# drv.net
KiCad netlist of a schematic drawn in Altium Designer
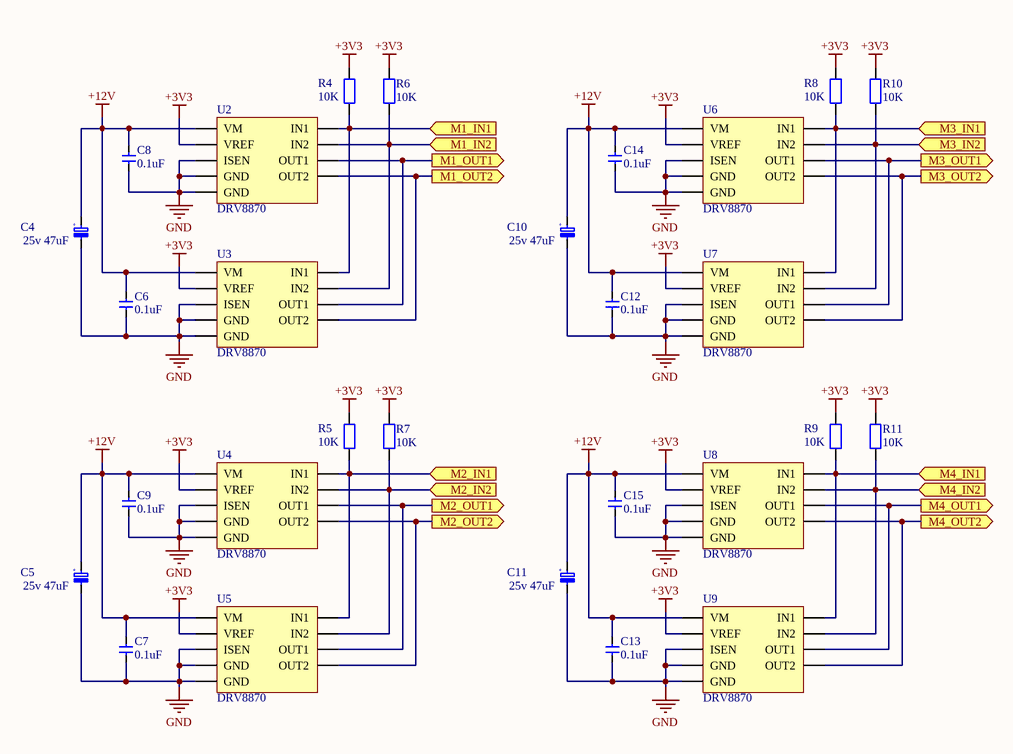
[diagram p0: drv.SchDoc]

(export (version "E")
  (design (tool "Eeschema 10.0.6"))
  (components
    (comp (ref "C4")
      (value "25v 47uF")
      (footprint "CAP_TANT_D")
      (description "Tantal SMD Cap")
      (libsource (lib "Asterisk") (part "CAP Tantal"))
    )
    (comp (ref "C5")
      (value "25v 47uF")
      (footprint "CAP_TANT_D")
      (description "Tantal SMD Cap")
      (libsource (lib "Asterisk") (part "CAP Tantal"))
    )
    (comp (ref "C6")
      (value "0.1uF")
      (footprint "CAP0805")
      (description "Ceramic SMD Cap")
      (libsource (lib "Asterisk") (part "CAP Ceramic"))
    )
    (comp (ref "C7")
      (value "0.1uF")
      (footprint "CAP0805")
      (description "Ceramic SMD Cap")
      (libsource (lib "Asterisk") (part "CAP Ceramic"))
    )
    (comp (ref "C8")
      (value "0.1uF")
      (footprint "CAP0805")
      (description "Ceramic SMD Cap")
      (libsource (lib "Asterisk") (part "CAP Ceramic"))
    )
    (comp (ref "C9")
      (value "0.1uF")
      (footprint "CAP0805")
      (description "Ceramic SMD Cap")
      (libsource (lib "Asterisk") (part "CAP Ceramic"))
    )
    (comp (ref "C10")
      (value "25v 47uF")
      (footprint "CAP_TANT_D")
      (description "Tantal SMD Cap")
      (libsource (lib "Asterisk") (part "CAP Tantal"))
    )
    (comp (ref "C11")
      (value "25v 47uF")
      (footprint "CAP_TANT_D")
      (description "Tantal SMD Cap")
      (libsource (lib "Asterisk") (part "CAP Tantal"))
    )
    (comp (ref "C12")
      (value "0.1uF")
      (footprint "CAP0805")
      (description "Ceramic SMD Cap")
      (libsource (lib "Asterisk") (part "CAP Ceramic"))
    )
    (comp (ref "C13")
      (value "0.1uF")
      (footprint "CAP0805")
      (description "Ceramic SMD Cap")
      (libsource (lib "Asterisk") (part "CAP Ceramic"))
    )
    (comp (ref "C14")
      (value "0.1uF")
      (footprint "CAP0805")
      (description "Ceramic SMD Cap")
      (libsource (lib "Asterisk") (part "CAP Ceramic"))
    )
    (comp (ref "C15")
      (value "0.1uF")
      (footprint "CAP0805")
      (description "Ceramic SMD Cap")
      (libsource (lib "Asterisk") (part "CAP Ceramic"))
    )
    (comp (ref "R4")
      (value "10K")
      (footprint "RES0805")
      (description "RES smd")
      (libsource (lib "Asterisk") (part "RES"))
    )
    (comp (ref "R5")
      (value "10K")
      (footprint "RES0805")
      (description "RES smd")
      (libsource (lib "Asterisk") (part "RES"))
    )
    (comp (ref "R6")
      (value "10K")
      (footprint "RES0805")
      (description "RES smd")
      (libsource (lib "Asterisk") (part "RES"))
    )
    (comp (ref "R7")
      (value "10K")
      (footprint "RES0805")
      (description "RES smd")
      (libsource (lib "Asterisk") (part "RES"))
    )
    (comp (ref "R8")
      (value "10K")
      (footprint "RES0805")
      (description "RES smd")
      (libsource (lib "Asterisk") (part "RES"))
    )
    (comp (ref "R9")
      (value "10K")
      (footprint "RES0805")
      (description "RES smd")
      (libsource (lib "Asterisk") (part "RES"))
    )
    (comp (ref "R10")
      (value "10K")
      (footprint "RES0805")
      (description "RES smd")
      (libsource (lib "Asterisk") (part "RES"))
    )
    (comp (ref "R11")
      (value "10K")
      (footprint "RES0805")
      (description "RES smd")
      (libsource (lib "Asterisk") (part "RES"))
    )
    (comp (ref "U2")
      (value "DRV8870")
      (footprint "DRV8870")
      (description "DC motor driver 3.6A")
      (libsource (lib "Asterisk") (part "DRV8870"))
    )
    (comp (ref "U3")
      (value "DRV8870")
      (footprint "DRV8870")
      (description "DC motor driver 3.6A")
      (libsource (lib "Asterisk") (part "DRV8870"))
    )
    (comp (ref "U4")
      (value "DRV8870")
      (footprint "DRV8870")
      (description "DC motor driver 3.6A")
      (libsource (lib "Asterisk") (part "DRV8870"))
    )
    (comp (ref "U5")
      (value "DRV8870")
      (footprint "DRV8870")
      (description "DC motor driver 3.6A")
      (libsource (lib "Asterisk") (part "DRV8870"))
    )
    (comp (ref "U6")
      (value "DRV8870")
      (footprint "DRV8870")
      (description "DC motor driver 3.6A")
      (libsource (lib "Asterisk") (part "DRV8870"))
    )
    (comp (ref "U7")
      (value "DRV8870")
      (footprint "DRV8870")
      (description "DC motor driver 3.6A")
      (libsource (lib "Asterisk") (part "DRV8870"))
    )
    (comp (ref "U8")
      (value "DRV8870")
      (footprint "DRV8870")
      (description "DC motor driver 3.6A")
      (libsource (lib "Asterisk") (part "DRV8870"))
    )
    (comp (ref "U9")
      (value "DRV8870")
      (footprint "DRV8870")
      (description "DC motor driver 3.6A")
      (libsource (lib "Asterisk") (part "DRV8870"))
    )
  )
  (nets
    (net (code "1") (name "+3V3") (class "Default")
      (node (ref "R10") (pin "2") (pinfunction "2_2") (pintype "passive"))
      (node (ref "R11") (pin "2") (pinfunction "2_2") (pintype "passive"))
      (node (ref "R4") (pin "2") (pinfunction "2_2") (pintype "passive"))
      (node (ref "R5") (pin "2") (pinfunction "2_2") (pintype "passive"))
      (node (ref "R6") (pin "2") (pinfunction "2_2") (pintype "passive"))
      (node (ref "R7") (pin "2") (pinfunction "2_2") (pintype "passive"))
      (node (ref "R8") (pin "2") (pinfunction "2_2") (pintype "passive"))
      (node (ref "R9") (pin "2") (pinfunction "2_2") (pintype "passive"))
      (node (ref "U2") (pin "4") (pinfunction "VREF_4") (pintype "passive"))
      (node (ref "U3") (pin "4") (pinfunction "VREF_4") (pintype "passive"))
      (node (ref "U4") (pin "4") (pinfunction "VREF_4") (pintype "passive"))
      (node (ref "U5") (pin "4") (pinfunction "VREF_4") (pintype "passive"))
      (node (ref "U6") (pin "4") (pinfunction "VREF_4") (pintype "passive"))
      (node (ref "U7") (pin "4") (pinfunction "VREF_4") (pintype "passive"))
      (node (ref "U8") (pin "4") (pinfunction "VREF_4") (pintype "passive"))
      (node (ref "U9") (pin "4") (pinfunction "VREF_4") (pintype "passive"))
    )
    (net (code "2") (name "+12V") (class "Default")
      (node (ref "C10") (pin "2") (pinfunction "PLUS_2") (pintype "passive"))
      (node (ref "C11") (pin "2") (pinfunction "PLUS_2") (pintype "passive"))
      (node (ref "C12") (pin "2") (pinfunction "2_2") (pintype "passive"))
      (node (ref "C13") (pin "2") (pinfunction "2_2") (pintype "passive"))
      (node (ref "C14") (pin "2") (pinfunction "2_2") (pintype "passive"))
      (node (ref "C15") (pin "2") (pinfunction "2_2") (pintype "passive"))
      (node (ref "C4") (pin "2") (pinfunction "PLUS_2") (pintype "passive"))
      (node (ref "C5") (pin "2") (pinfunction "PLUS_2") (pintype "passive"))
      (node (ref "C6") (pin "2") (pinfunction "2_2") (pintype "passive"))
      (node (ref "C7") (pin "2") (pinfunction "2_2") (pintype "passive"))
      (node (ref "C8") (pin "2") (pinfunction "2_2") (pintype "passive"))
      (node (ref "C9") (pin "2") (pinfunction "2_2") (pintype "passive"))
      (node (ref "U2") (pin "5") (pinfunction "VM_5") (pintype "passive"))
      (node (ref "U3") (pin "5") (pinfunction "VM_5") (pintype "passive"))
      (node (ref "U4") (pin "5") (pinfunction "VM_5") (pintype "passive"))
      (node (ref "U5") (pin "5") (pinfunction "VM_5") (pintype "passive"))
      (node (ref "U6") (pin "5") (pinfunction "VM_5") (pintype "passive"))
      (node (ref "U7") (pin "5") (pinfunction "VM_5") (pintype "passive"))
      (node (ref "U8") (pin "5") (pinfunction "VM_5") (pintype "passive"))
      (node (ref "U9") (pin "5") (pinfunction "VM_5") (pintype "passive"))
    )
    (net (code "3") (name "/M1_IN1") (class "Default")
      (node (ref "R4") (pin "1") (pinfunction "1_1") (pintype "passive"))
      (node (ref "U2") (pin "2") (pinfunction "IN1_2") (pintype "passive"))
      (node (ref "U3") (pin "2") (pinfunction "IN1_2") (pintype "passive"))
    )
    (net (code "4") (name "/M1_IN2") (class "Default")
      (node (ref "R6") (pin "1") (pinfunction "1_1") (pintype "passive"))
      (node (ref "U2") (pin "3") (pinfunction "IN2_3") (pintype "passive"))
      (node (ref "U3") (pin "3") (pinfunction "IN2_3") (pintype "passive"))
    )
    (net (code "5") (name "/M1_OUT1") (class "Default")
      (node (ref "U2") (pin "6") (pinfunction "OUT1_6") (pintype "passive"))
      (node (ref "U3") (pin "6") (pinfunction "OUT1_6") (pintype "passive"))
    )
    (net (code "6") (name "/M1_OUT2") (class "Default")
      (node (ref "U2") (pin "8") (pinfunction "OUT2_8") (pintype "passive"))
      (node (ref "U3") (pin "8") (pinfunction "OUT2_8") (pintype "passive"))
    )
    (net (code "7") (name "/M2_IN1") (class "Default")
      (node (ref "R5") (pin "1") (pinfunction "1_1") (pintype "passive"))
      (node (ref "U4") (pin "2") (pinfunction "IN1_2") (pintype "passive"))
      (node (ref "U5") (pin "2") (pinfunction "IN1_2") (pintype "passive"))
    )
    (net (code "8") (name "/M2_IN2") (class "Default")
      (node (ref "R7") (pin "1") (pinfunction "1_1") (pintype "passive"))
      (node (ref "U4") (pin "3") (pinfunction "IN2_3") (pintype "passive"))
      (node (ref "U5") (pin "3") (pinfunction "IN2_3") (pintype "passive"))
    )
    (net (code "9") (name "/M2_OUT1") (class "Default")
      (node (ref "U4") (pin "6") (pinfunction "OUT1_6") (pintype "passive"))
      (node (ref "U5") (pin "6") (pinfunction "OUT1_6") (pintype "passive"))
    )
    (net (code "10") (name "/M2_OUT2") (class "Default")
      (node (ref "U4") (pin "8") (pinfunction "OUT2_8") (pintype "passive"))
      (node (ref "U5") (pin "8") (pinfunction "OUT2_8") (pintype "passive"))
    )
    (net (code "11") (name "/M3_IN1") (class "Default")
      (node (ref "R8") (pin "1") (pinfunction "1_1") (pintype "passive"))
      (node (ref "U6") (pin "2") (pinfunction "IN1_2") (pintype "passive"))
      (node (ref "U7") (pin "2") (pinfunction "IN1_2") (pintype "passive"))
    )
    (net (code "12") (name "/M3_IN2") (class "Default")
      (node (ref "R10") (pin "1") (pinfunction "1_1") (pintype "passive"))
      (node (ref "U6") (pin "3") (pinfunction "IN2_3") (pintype "passive"))
      (node (ref "U7") (pin "3") (pinfunction "IN2_3") (pintype "passive"))
    )
    (net (code "13") (name "/M3_OUT1") (class "Default")
      (node (ref "U6") (pin "6") (pinfunction "OUT1_6") (pintype "passive"))
      (node (ref "U7") (pin "6") (pinfunction "OUT1_6") (pintype "passive"))
    )
    (net (code "14") (name "/M3_OUT2") (class "Default")
      (node (ref "U6") (pin "8") (pinfunction "OUT2_8") (pintype "passive"))
      (node (ref "U7") (pin "8") (pinfunction "OUT2_8") (pintype "passive"))
    )
    (net (code "15") (name "/M4_IN1") (class "Default")
      (node (ref "R9") (pin "1") (pinfunction "1_1") (pintype "passive"))
      (node (ref "U8") (pin "2") (pinfunction "IN1_2") (pintype "passive"))
      (node (ref "U9") (pin "2") (pinfunction "IN1_2") (pintype "passive"))
    )
    (net (code "16") (name "/M4_IN2") (class "Default")
      (node (ref "R11") (pin "1") (pinfunction "1_1") (pintype "passive"))
      (node (ref "U8") (pin "3") (pinfunction "IN2_3") (pintype "passive"))
      (node (ref "U9") (pin "3") (pinfunction "IN2_3") (pintype "passive"))
    )
    (net (code "17") (name "/M4_OUT1") (class "Default")
      (node (ref "U8") (pin "6") (pinfunction "OUT1_6") (pintype "passive"))
      (node (ref "U9") (pin "6") (pinfunction "OUT1_6") (pintype "passive"))
    )
    (net (code "18") (name "/M4_OUT2") (class "Default")
      (node (ref "U8") (pin "8") (pinfunction "OUT2_8") (pintype "passive"))
      (node (ref "U9") (pin "8") (pinfunction "OUT2_8") (pintype "passive"))
    )
    (net (code "19") (name "GND") (class "Default")
      (node (ref "C10") (pin "1") (pinfunction "MINUS_1") (pintype "passive"))
      (node (ref "C11") (pin "1") (pinfunction "MINUS_1") (pintype "passive"))
      (node (ref "C12") (pin "1") (pinfunction "1_1") (pintype "passive"))
      (node (ref "C13") (pin "1") (pinfunction "1_1") (pintype "passive"))
      (node (ref "C14") (pin "1") (pinfunction "1_1") (pintype "passive"))
      (node (ref "C15") (pin "1") (pinfunction "1_1") (pintype "passive"))
      (node (ref "C4") (pin "1") (pinfunction "MINUS_1") (pintype "passive"))
      (node (ref "C5") (pin "1") (pinfunction "MINUS_1") (pintype "passive"))
      (node (ref "C6") (pin "1") (pinfunction "1_1") (pintype "passive"))
      (node (ref "C7") (pin "1") (pinfunction "1_1") (pintype "passive"))
      (node (ref "C8") (pin "1") (pinfunction "1_1") (pintype "passive"))
      (node (ref "C9") (pin "1") (pinfunction "1_1") (pintype "passive"))
      (node (ref "U2") (pin "1") (pinfunction "GND_1") (pintype "passive"))
      (node (ref "U2") (pin "7") (pinfunction "ISEN_7") (pintype "passive"))
      (node (ref "U2") (pin "9") (pinfunction "GND_9") (pintype "passive"))
      (node (ref "U3") (pin "1") (pinfunction "GND_1") (pintype "passive"))
      (node (ref "U3") (pin "7") (pinfunction "ISEN_7") (pintype "passive"))
      (node (ref "U3") (pin "9") (pinfunction "GND_9") (pintype "passive"))
      (node (ref "U4") (pin "1") (pinfunction "GND_1") (pintype "passive"))
      (node (ref "U4") (pin "7") (pinfunction "ISEN_7") (pintype "passive"))
      (node (ref "U4") (pin "9") (pinfunction "GND_9") (pintype "passive"))
      (node (ref "U5") (pin "1") (pinfunction "GND_1") (pintype "passive"))
      (node (ref "U5") (pin "7") (pinfunction "ISEN_7") (pintype "passive"))
      (node (ref "U5") (pin "9") (pinfunction "GND_9") (pintype "passive"))
      (node (ref "U6") (pin "1") (pinfunction "GND_1") (pintype "passive"))
      (node (ref "U6") (pin "7") (pinfunction "ISEN_7") (pintype "passive"))
      (node (ref "U6") (pin "9") (pinfunction "GND_9") (pintype "passive"))
      (node (ref "U7") (pin "1") (pinfunction "GND_1") (pintype "passive"))
      (node (ref "U7") (pin "7") (pinfunction "ISEN_7") (pintype "passive"))
      (node (ref "U7") (pin "9") (pinfunction "GND_9") (pintype "passive"))
      (node (ref "U8") (pin "1") (pinfunction "GND_1") (pintype "passive"))
      (node (ref "U8") (pin "7") (pinfunction "ISEN_7") (pintype "passive"))
      (node (ref "U8") (pin "9") (pinfunction "GND_9") (pintype "passive"))
      (node (ref "U9") (pin "1") (pinfunction "GND_1") (pintype "passive"))
      (node (ref "U9") (pin "7") (pinfunction "ISEN_7") (pintype "passive"))
      (node (ref "U9") (pin "9") (pinfunction "GND_9") (pintype "passive"))
    )
  )
)
